# kicker.net
KiCad netlist of a schematic drawn in EAGLE
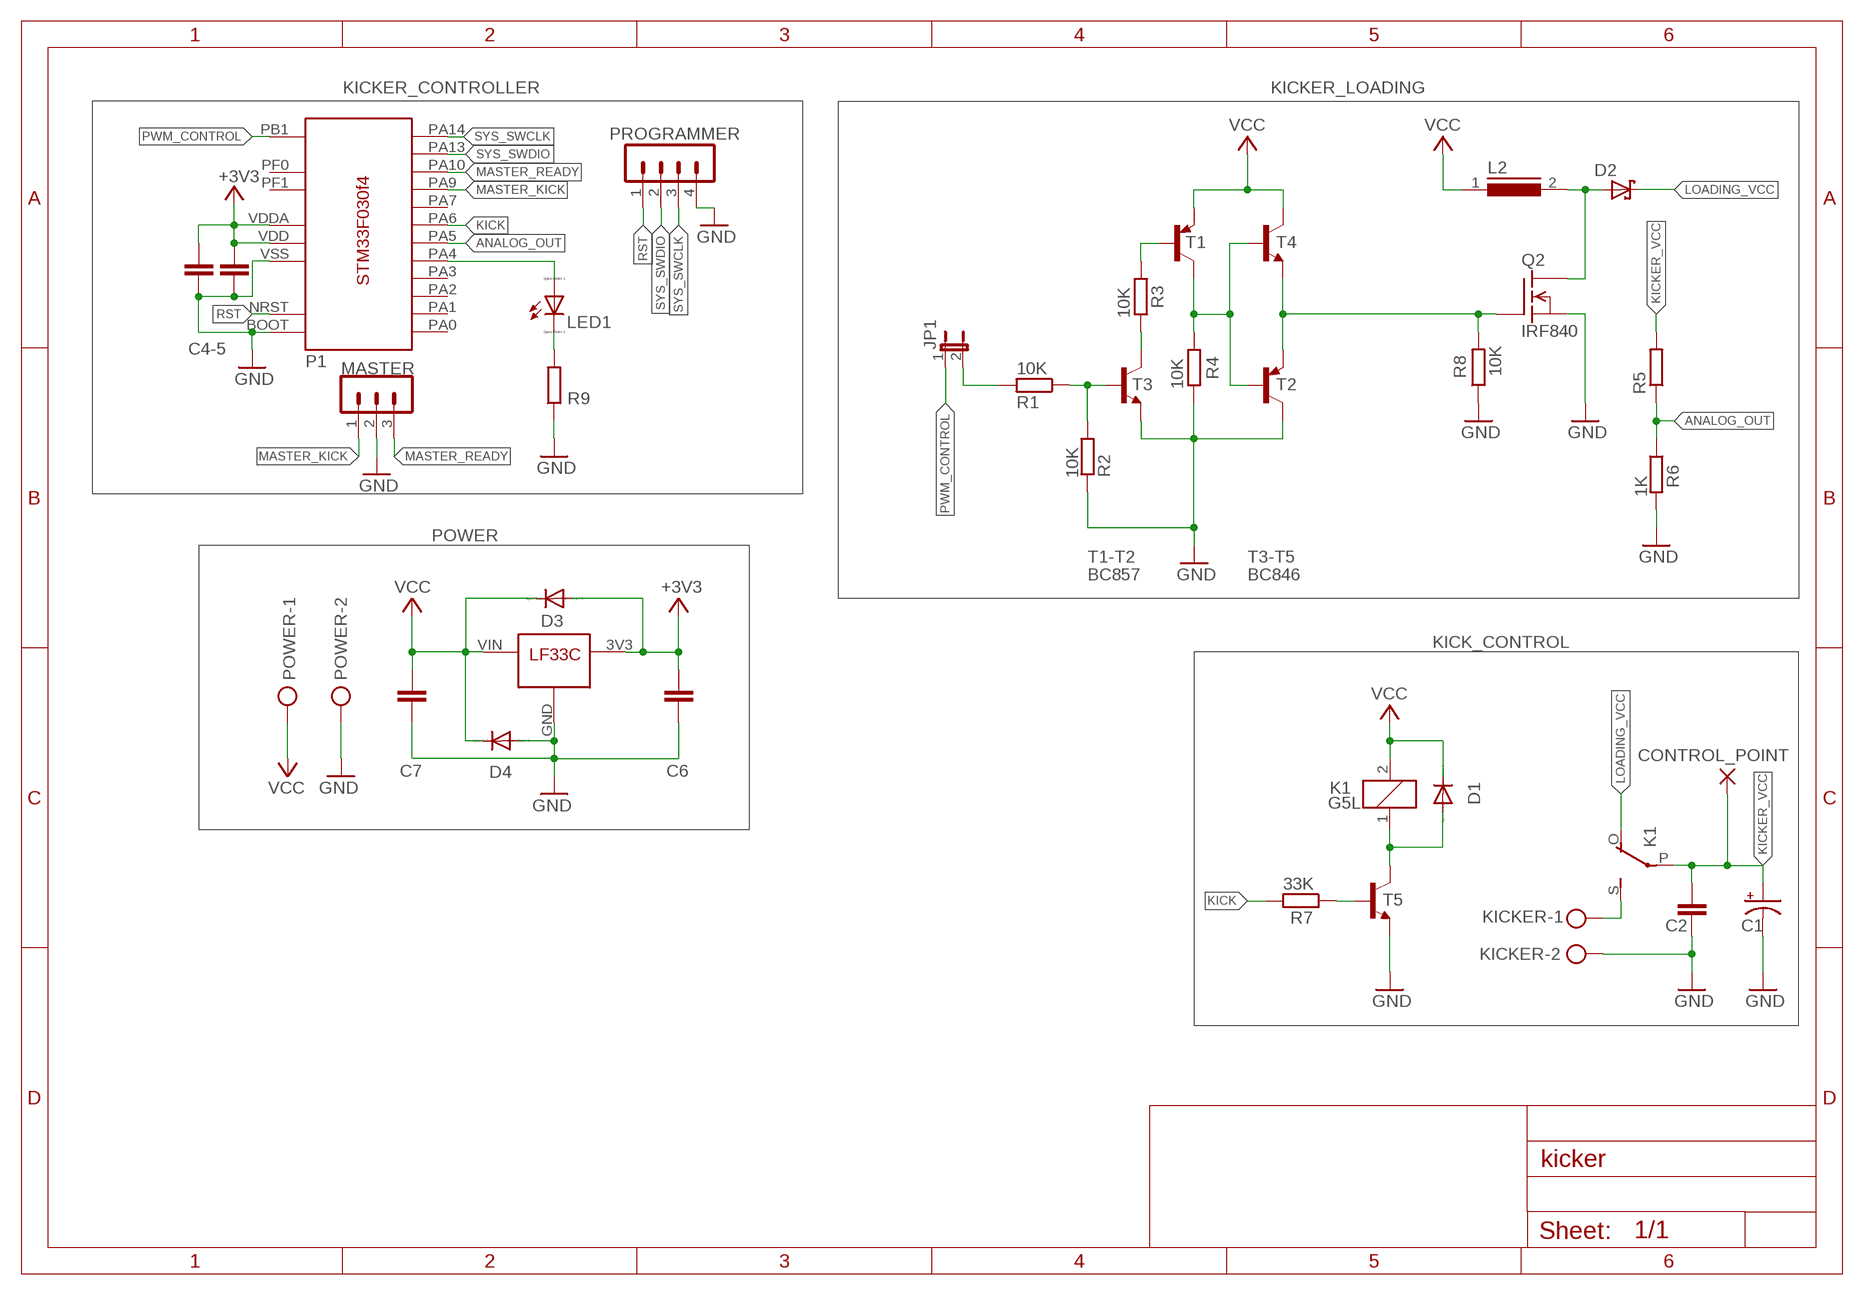
[diagram p0: schematic, sheet 1]

(export (version "E")
  (design (tool "Eeschema 10.0.6"))
  (components
    (comp (ref "C1")
      (value "CPOL-USE10-30")
      (footprint "eagle-import:EB30D")
      (libsource (lib "eagle-import") (part "CPOL-USE10-30"))
    )
    (comp (ref "C2")
      (value "C-EU275-113X316")
      (footprint "eagle-import:C275-113X316")
      (libsource (lib "eagle-import") (part "C-EU275-113X316"))
    )
    (comp (ref "C4")
      (value "100K")
      (footprint "eagle-import:C0603")
      (libsource (lib "eagle-import") (part "C-EUC0603"))
    )
    (comp (ref "C5")
      (value "100K")
      (footprint "eagle-import:C0603")
      (libsource (lib "eagle-import") (part "C-EUC0603"))
    )
    (comp (ref "C6")
      (value "100k")
      (footprint "eagle-import:C0603")
      (libsource (lib "eagle-import") (part "C-EUC0603"))
    )
    (comp (ref "C7")
      (value "100k")
      (footprint "eagle-import:C0603")
      (libsource (lib "eagle-import") (part "C-EUC0603"))
    )
    (comp (ref "CONTROL_POINT")
      (value "3,81/1,4")
      (footprint "eagle-import:3,81_1,4")
      (libsource (lib "eagle-import") (part "3,81/1,4"))
    )
    (comp (ref "D1")
      (value "DIODE-MINIMELF")
      (footprint "eagle-import:MINIMELF")
      (libsource (lib "eagle-import") (part "DIODE-MINIMELF"))
    )
    (comp (ref "D2")
      (value "1N6267A")
      (footprint "eagle-import:C4111-15")
      (libsource (lib "eagle-import") (part "1N6267A"))
    )
    (comp (ref "D3")
      (value "DIODE-MINIMELF")
      (footprint "eagle-import:MINIMELF")
      (libsource (lib "eagle-import") (part "DIODE-MINIMELF"))
    )
    (comp (ref "D4")
      (value "DIODE-MINIMELF")
      (footprint "eagle-import:MINIMELF")
      (libsource (lib "eagle-import") (part "DIODE-MINIMELF"))
    )
    (comp (ref "JP1")
      (value "JP1E")
      (footprint "eagle-import:JP1")
      (libsource (lib "eagle-import") (part "JP1E"))
    )
    (comp (ref "K1")
      (value "G5L")
      (footprint "eagle-import:G5LE")
      (libsource (lib "eagle-import") (part "G5L"))
    )
    (comp (ref "KICKER")
      (value "W237-102")
      (footprint "eagle-import:W237-102")
      (fields (field (name "MPN") "237-102"))
      (libsource (lib "eagle-import") (part "W237-102"))
    )
    (comp (ref "L2")
      (value "SFT830S")
      (footprint "eagle-import:SFT830S")
      (libsource (lib "eagle-import") (part "SFT830S"))
    )
    (comp (ref "LED1")
      (value "LED_E")
      (footprint "eagle-import:LED_1206")
      (libsource (lib "eagle-import") (part "LED_E"))
    )
    (comp (ref "MASTER")
      (value "MA03-1")
      (footprint "eagle-import:MA03-1")
      (libsource (lib "eagle-import") (part "MA03-1"))
    )
    (comp (ref "P1")
      (value "STM32F030F4")
      (footprint "eagle-import:STM32F030F4")
      (libsource (lib "eagle-import") (part "STM32F030F4"))
    )
    (comp (ref "POWER")
      (value "W237-102")
      (footprint "eagle-import:W237-102")
      (fields (field (name "MPN") "237-102"))
      (libsource (lib "eagle-import") (part "W237-102"))
    )
    (comp (ref "PROGRAMMER")
      (value "MA04-1")
      (footprint "eagle-import:MA04-1")
      (libsource (lib "eagle-import") (part "MA04-1"))
    )
    (comp (ref "Q2")
      (value "IRF840")
      (footprint "eagle-import:TO220")
      (libsource (lib "eagle-import") (part "IRF840"))
    )
    (comp (ref "R1")
      (value "10K")
      (footprint "eagle-import:R0603")
      (libsource (lib "eagle-import") (part "R-EU_R0603"))
    )
    (comp (ref "R2")
      (value "10K")
      (footprint "eagle-import:R0603")
      (libsource (lib "eagle-import") (part "R-EU_R0603"))
    )
    (comp (ref "R3")
      (value "10K")
      (footprint "eagle-import:R0603")
      (libsource (lib "eagle-import") (part "R-EU_R0603"))
    )
    (comp (ref "R4")
      (value "10K")
      (footprint "eagle-import:R0603")
      (libsource (lib "eagle-import") (part "R-EU_R0603"))
    )
    (comp (ref "R5")
      (value "R-EU_0309/10")
      (footprint "eagle-import:0309_10")
      (libsource (lib "eagle-import") (part "R-EU_0309/10"))
    )
    (comp (ref "R6")
      (value "1K")
      (footprint "eagle-import:R0603")
      (libsource (lib "eagle-import") (part "R-EU_R0603"))
    )
    (comp (ref "R7")
      (value "33K")
      (footprint "eagle-import:R0603")
      (libsource (lib "eagle-import") (part "R-EU_R0603"))
    )
    (comp (ref "R8")
      (value "10K")
      (footprint "eagle-import:R0603")
      (libsource (lib "eagle-import") (part "R-EU_R0603"))
    )
    (comp (ref "R9")
      (value "R-EU_R0603")
      (footprint "eagle-import:R0603")
      (libsource (lib "eagle-import") (part "R-EU_R0603"))
    )
    (comp (ref "T1")
      (value "BC856A-PNP-SOT23-BEC")
      (footprint "eagle-import:SOT23-BEC")
      (libsource (lib "eagle-import") (part "-PNP-SOT23-BECBC856A"))
    )
    (comp (ref "T2")
      (value "BC856A-PNP-SOT23-BEC")
      (footprint "eagle-import:SOT23-BEC")
      (libsource (lib "eagle-import") (part "-PNP-SOT23-BECBC856A"))
    )
    (comp (ref "T3")
      (value "BC847")
      (footprint "eagle-import:SOT23")
      (libsource (lib "eagle-import") (part "BC847"))
    )
    (comp (ref "T4")
      (value "BC847")
      (footprint "eagle-import:SOT23")
      (libsource (lib "eagle-import") (part "BC847"))
    )
    (comp (ref "T5")
      (value "BC847")
      (footprint "eagle-import:SOT23")
      (libsource (lib "eagle-import") (part "BC847"))
    )
    (comp (ref "U$1")
      (value "LF33C")
      (footprint "eagle-import:LF33C")
      (libsource (lib "eagle-import") (part "LF33C"))
    )
  )
  (nets
    (net (code "1") (name "+3V3") (class "Default")
      (node (ref "C4") (pin "1") (pinfunction "1_1") (pintype "passive"))
      (node (ref "C5") (pin "1") (pinfunction "1_1") (pintype "passive"))
      (node (ref "C6") (pin "1") (pinfunction "1_1") (pintype "passive"))
      (node (ref "D3") (pin "A") (pinfunction "A_A") (pintype "passive"))
      (node (ref "P1") (pin "VDD") (pinfunction "VDD_VDD") (pintype "bidirectional"))
      (node (ref "P1") (pin "VDDA") (pinfunction "VDDA_VDDA") (pintype "bidirectional"))
      (node (ref "U$1") (pin "3V3") (pinfunction "3V3_3V3") (pintype "bidirectional"))
    )
    (net (code "2") (name "ANALOG_OUT") (class "Default")
      (node (ref "P1") (pin "PA5") (pinfunction "PA5_PA5") (pintype "bidirectional"))
      (node (ref "R5") (pin "1") (pinfunction "1_1") (pintype "passive"))
      (node (ref "R6") (pin "1") (pinfunction "1_1") (pintype "passive"))
    )
    (net (code "3") (name "GND") (class "Default")
      (node (ref "C1") (pin "-") (pinfunction "-_-") (pintype "passive"))
      (node (ref "C2") (pin "2") (pinfunction "2_2") (pintype "passive"))
      (node (ref "C4") (pin "2") (pinfunction "2_2") (pintype "passive"))
      (node (ref "C5") (pin "2") (pinfunction "2_2") (pintype "passive"))
      (node (ref "C6") (pin "2") (pinfunction "2_2") (pintype "passive"))
      (node (ref "C7") (pin "2") (pinfunction "2_2") (pintype "passive"))
      (node (ref "D4") (pin "A") (pinfunction "A_A") (pintype "passive"))
      (node (ref "KICKER") (pin "2") (pinfunction "KL_2") (pintype "passive"))
      (node (ref "MASTER") (pin "2") (pinfunction "2_2") (pintype "passive"))
      (node (ref "P1") (pin "BOOT") (pinfunction "BOOT_BOOT") (pintype "bidirectional"))
      (node (ref "P1") (pin "VSS") (pinfunction "VSS_VSS") (pintype "bidirectional"))
      (node (ref "POWER") (pin "2") (pinfunction "KL_2") (pintype "passive"))
      (node (ref "PROGRAMMER") (pin "4") (pinfunction "4_4") (pintype "passive"))
      (node (ref "Q2") (pin "3") (pinfunction "S_3") (pintype "passive"))
      (node (ref "R2") (pin "2") (pinfunction "2_2") (pintype "passive"))
      (node (ref "R4") (pin "2") (pinfunction "2_2") (pintype "passive"))
      (node (ref "R6") (pin "2") (pinfunction "2_2") (pintype "passive"))
      (node (ref "R8") (pin "1") (pinfunction "1_1") (pintype "passive"))
      (node (ref "R9") (pin "1") (pinfunction "1_1") (pintype "passive"))
      (node (ref "T2") (pin "C") (pinfunction "C_C") (pintype "passive"))
      (node (ref "T3") (pin "2") (pinfunction "E_2") (pintype "passive"))
      (node (ref "T5") (pin "2") (pinfunction "E_2") (pintype "passive"))
      (node (ref "U$1") (pin "GND") (pinfunction "GND_GND") (pintype "bidirectional"))
    )
    (net (code "4") (name "KICK") (class "Default")
      (node (ref "P1") (pin "PA6") (pinfunction "PA6_PA6") (pintype "bidirectional"))
      (node (ref "R7") (pin "2") (pinfunction "2_2") (pintype "passive"))
    )
    (net (code "5") (name "KICKER_VCC") (class "Default")
      (node (ref "C1") (pin "+") (pinfunction "+_+") (pintype "passive"))
      (node (ref "C2") (pin "1") (pinfunction "1_1") (pintype "passive"))
      (node (ref "CONTROL_POINT") (pin "1") (pinfunction "P_1") (pintype "passive"))
      (node (ref "K1") (pin "P") (pinfunction "P_P") (pintype "passive"))
      (node (ref "R5") (pin "2") (pinfunction "2_2") (pintype "passive"))
    )
    (net (code "6") (name "LOADING_VCC") (class "Default")
      (node (ref "D2") (pin "C") (pinfunction "C_C") (pintype "passive"))
      (node (ref "K1") (pin "O") (pinfunction "O_O") (pintype "passive"))
    )
    (net (code "7") (name "MASTER_KICK") (class "Default")
      (node (ref "MASTER") (pin "1") (pinfunction "1_1") (pintype "passive"))
      (node (ref "P1") (pin "PA9") (pinfunction "PA9_PA9") (pintype "bidirectional"))
    )
    (net (code "8") (name "MASTER_READY") (class "Default")
      (node (ref "MASTER") (pin "3") (pinfunction "3_3") (pintype "passive"))
      (node (ref "P1") (pin "PA10") (pinfunction "PA10_PA10") (pintype "bidirectional"))
    )
    (net (code "9") (name "Net-(JP1-Pad2)") (class "Default")
      (node (ref "JP1") (pin "2") (pinfunction "2_2") (pintype "passive"))
      (node (ref "R1") (pin "2") (pinfunction "2_2") (pintype "passive"))
    )
    (net (code "10") (name "Net-(KICKERA-KL)") (class "Default")
      (node (ref "K1") (pin "S") (pinfunction "S_S") (pintype "passive"))
      (node (ref "KICKER") (pin "1") (pinfunction "KL_1") (pintype "passive"))
    )
    (net (code "11") (name "Net-(LED1-PadA)") (class "Default")
      (node (ref "LED1") (pin "A") (pinfunction "A_A") (pintype "passive"))
      (node (ref "P1") (pin "PA4") (pinfunction "PA4_PA4") (pintype "bidirectional"))
    )
    (net (code "12") (name "Net-(LED1-PadC)") (class "Default")
      (node (ref "LED1") (pin "C") (pinfunction "C_C") (pintype "passive"))
      (node (ref "R9") (pin "2") (pinfunction "2_2") (pintype "passive"))
    )
    (net (code "13") (name "Net-(Q2-D)") (class "Default")
      (node (ref "D2") (pin "A") (pinfunction "A_A") (pintype "passive"))
      (node (ref "L2") (pin "2") (pinfunction "2_2") (pintype "passive"))
      (node (ref "Q2") (pin "2") (pinfunction "D_2") (pintype "passive"))
    )
    (net (code "14") (name "Net-(Q2-G)") (class "Default")
      (node (ref "Q2") (pin "1") (pinfunction "G_1") (pintype "passive"))
      (node (ref "R8") (pin "2") (pinfunction "2_2") (pintype "passive"))
      (node (ref "T2") (pin "E") (pinfunction "E_E") (pintype "passive"))
      (node (ref "T4") (pin "2") (pinfunction "E_2") (pintype "passive"))
    )
    (net (code "15") (name "Net-(R3-Pad1)") (class "Default")
      (node (ref "R3") (pin "1") (pinfunction "1_1") (pintype "passive"))
      (node (ref "T1") (pin "B") (pinfunction "B_B") (pintype "passive"))
    )
    (net (code "16") (name "Net-(T3-B)") (class "Default")
      (node (ref "R1") (pin "1") (pinfunction "1_1") (pintype "passive"))
      (node (ref "R2") (pin "1") (pinfunction "1_1") (pintype "passive"))
      (node (ref "T3") (pin "1") (pinfunction "B_1") (pintype "passive"))
    )
    (net (code "17") (name "Net-(T3-C)") (class "Default")
      (node (ref "R3") (pin "2") (pinfunction "2_2") (pintype "passive"))
      (node (ref "T3") (pin "3") (pinfunction "C_3") (pintype "passive"))
    )
    (net (code "18") (name "Net-(T4-B)") (class "Default")
      (node (ref "R4") (pin "1") (pinfunction "1_1") (pintype "passive"))
      (node (ref "T1") (pin "C") (pinfunction "C_C") (pintype "passive"))
      (node (ref "T2") (pin "B") (pinfunction "B_B") (pintype "passive"))
      (node (ref "T4") (pin "1") (pinfunction "B_1") (pintype "passive"))
    )
    (net (code "19") (name "Net-(T5-B)") (class "Default")
      (node (ref "R7") (pin "1") (pinfunction "1_1") (pintype "passive"))
      (node (ref "T5") (pin "1") (pinfunction "B_1") (pintype "passive"))
    )
    (net (code "20") (name "Net-(T5-C)") (class "Default")
      (node (ref "D1") (pin "A") (pinfunction "A_A") (pintype "passive"))
      (node (ref "K1") (pin "1") (pinfunction "1_1") (pintype "passive"))
      (node (ref "T5") (pin "3") (pinfunction "C_3") (pintype "passive"))
    )
    (net (code "21") (name "PWM_CONTROL") (class "Default")
      (node (ref "JP1") (pin "1") (pinfunction "1_1") (pintype "passive"))
      (node (ref "P1") (pin "PB1") (pinfunction "PB1_PB1") (pintype "bidirectional"))
    )
    (net (code "22") (name "RST") (class "Default")
      (node (ref "P1") (pin "NRST") (pinfunction "NRST_NRST") (pintype "bidirectional"))
      (node (ref "PROGRAMMER") (pin "1") (pinfunction "1_1") (pintype "passive"))
    )
    (net (code "23") (name "SYS_SWCLK") (class "Default")
      (node (ref "P1") (pin "PA14") (pinfunction "PA14_PA14") (pintype "bidirectional"))
      (node (ref "PROGRAMMER") (pin "3") (pinfunction "3_3") (pintype "passive"))
    )
    (net (code "24") (name "SYS_SWDIO") (class "Default")
      (node (ref "P1") (pin "PA13") (pinfunction "PA13_PA13") (pintype "bidirectional"))
      (node (ref "PROGRAMMER") (pin "2") (pinfunction "2_2") (pintype "passive"))
    )
    (net (code "25") (name "VCC") (class "Default")
      (node (ref "C7") (pin "1") (pinfunction "1_1") (pintype "passive"))
      (node (ref "D1") (pin "C") (pinfunction "C_C") (pintype "passive"))
      (node (ref "D3") (pin "C") (pinfunction "C_C") (pintype "passive"))
      (node (ref "D4") (pin "C") (pinfunction "C_C") (pintype "passive"))
      (node (ref "K1") (pin "2") (pinfunction "2_2") (pintype "passive"))
      (node (ref "L2") (pin "1") (pinfunction "1_1") (pintype "passive"))
      (node (ref "POWER") (pin "1") (pinfunction "KL_1") (pintype "passive"))
      (node (ref "T1") (pin "E") (pinfunction "E_E") (pintype "passive"))
      (node (ref "T4") (pin "3") (pinfunction "C_3") (pintype "passive"))
      (node (ref "U$1") (pin "VIN") (pinfunction "VIN_VIN") (pintype "bidirectional"))
    )
    (net (code "26") (name "unconnected-(P1-PadPA0)") (class "Default")
      (node (ref "P1") (pin "PA0") (pinfunction "PA0_PA0") (pintype "bidirectional"))
    )
    (net (code "27") (name "unconnected-(P1-PadPA1)") (class "Default")
      (node (ref "P1") (pin "PA1") (pinfunction "PA1_PA1") (pintype "bidirectional"))
    )
    (net (code "28") (name "unconnected-(P1-PadPA2)") (class "Default")
      (node (ref "P1") (pin "PA2") (pinfunction "PA2_PA2") (pintype "bidirectional"))
    )
    (net (code "29") (name "unconnected-(P1-PadPA3)") (class "Default")
      (node (ref "P1") (pin "PA3") (pinfunction "PA3_PA3") (pintype "bidirectional"))
    )
    (net (code "30") (name "unconnected-(P1-PadPA7)") (class "Default")
      (node (ref "P1") (pin "PA7") (pinfunction "PA7_PA7") (pintype "bidirectional"))
    )
    (net (code "31") (name "unconnected-(P1-PadPF0)") (class "Default")
      (node (ref "P1") (pin "PF0") (pinfunction "PF0_PF0") (pintype "bidirectional"))
    )
    (net (code "32") (name "unconnected-(P1-PadPF1)") (class "Default")
      (node (ref "P1") (pin "PF1") (pinfunction "PF1_PF1") (pintype "bidirectional"))
    )
  )
)
